# RSG_1_0.net
KiCad netlist of a schematic drawn in EAGLE
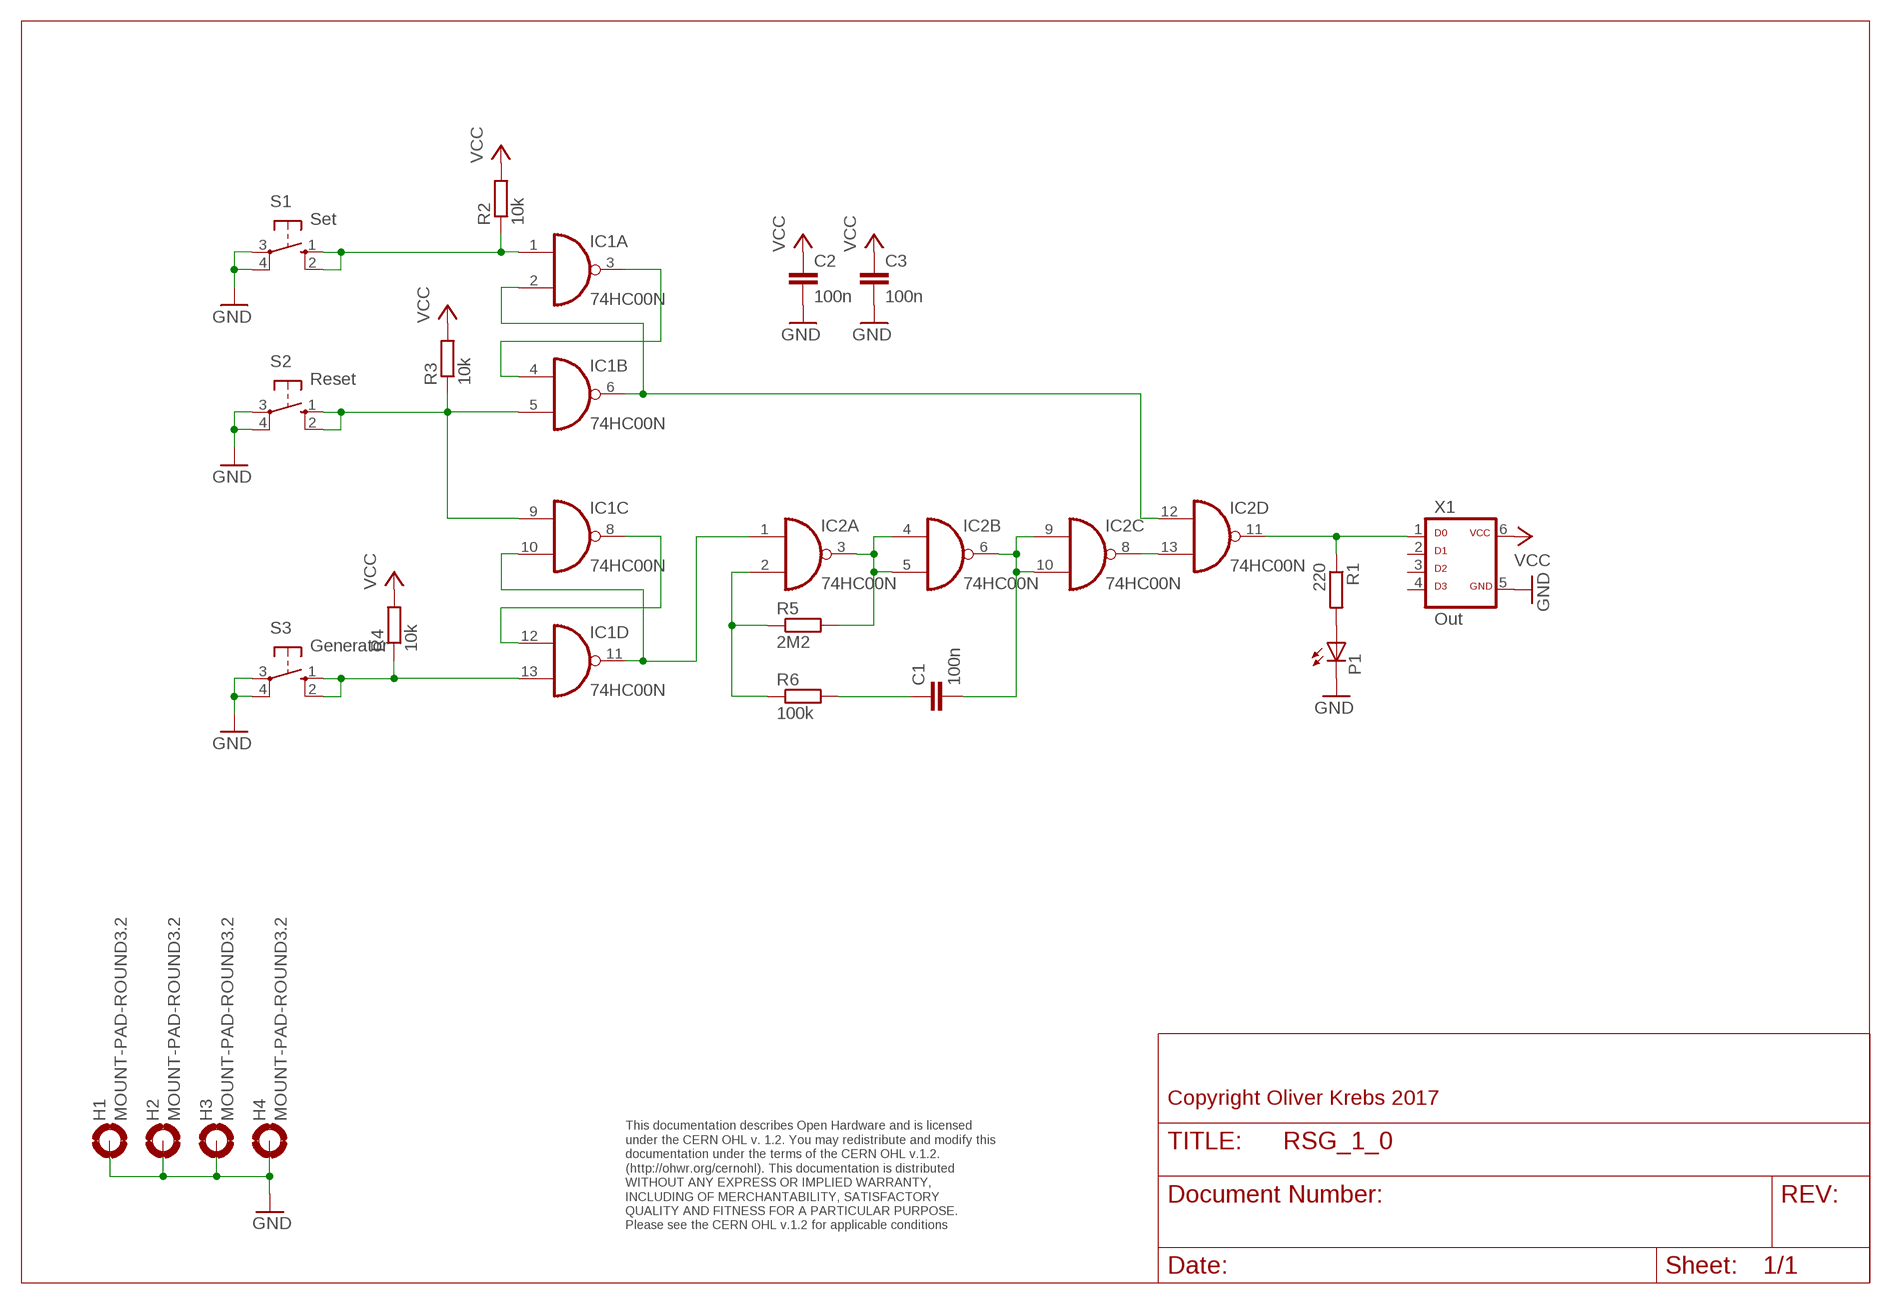
[diagram p0: schematic, sheet 1]

(export (version "E")
  (design (tool "Eeschema 10.0.6"))
  (components
    (comp (ref "C1")
      (value "100n")
      (footprint "eagle-import:C050-025X075")
      (libsource (lib "eagle-import") (part "C-EU050-025X075"))
    )
    (comp (ref "C2")
      (value "100n")
      (footprint "eagle-import:C050-025X075")
      (libsource (lib "eagle-import") (part "C-EU050-025X075"))
    )
    (comp (ref "C3")
      (value "100n")
      (footprint "eagle-import:C050-025X075")
      (libsource (lib "eagle-import") (part "C-EU050-025X075"))
    )
    (comp (ref "H1")
      (value "MOUNT-PAD-ROUND3.2")
      (footprint "eagle-import:3,2-PAD")
      (libsource (lib "eagle-import") (part "MOUNT-PAD-ROUND3.2"))
    )
    (comp (ref "H2")
      (value "MOUNT-PAD-ROUND3.2")
      (footprint "eagle-import:3,2-PAD")
      (libsource (lib "eagle-import") (part "MOUNT-PAD-ROUND3.2"))
    )
    (comp (ref "H3")
      (value "MOUNT-PAD-ROUND3.2")
      (footprint "eagle-import:3,2-PAD")
      (libsource (lib "eagle-import") (part "MOUNT-PAD-ROUND3.2"))
    )
    (comp (ref "H4")
      (value "MOUNT-PAD-ROUND3.2")
      (footprint "eagle-import:3,2-PAD")
      (libsource (lib "eagle-import") (part "MOUNT-PAD-ROUND3.2"))
    )
    (comp (ref "IC1")
      (value "74HC00N")
      (footprint "eagle-import:DIL14")
      (libsource (lib "eagle-import") (part "7400NHC"))
    )
    (comp (ref "IC2")
      (value "74HC00N")
      (footprint "eagle-import:DIL14")
      (libsource (lib "eagle-import") (part "7400NHC"))
    )
    (comp (ref "P1")
      (value "LED3MM")
      (footprint "eagle-import:LED3MM")
      (libsource (lib "eagle-import") (part "LED3MM"))
    )
    (comp (ref "R1")
      (value "220")
      (footprint "eagle-import:0207_10")
      (libsource (lib "eagle-import") (part "R-EU_0207/10"))
    )
    (comp (ref "R2")
      (value "10k")
      (footprint "eagle-import:0207_10")
      (libsource (lib "eagle-import") (part "R-EU_0207/10"))
    )
    (comp (ref "R3")
      (value "10k")
      (footprint "eagle-import:0207_10")
      (libsource (lib "eagle-import") (part "R-EU_0207/10"))
    )
    (comp (ref "R4")
      (value "10k")
      (footprint "eagle-import:0207_10")
      (libsource (lib "eagle-import") (part "R-EU_0207/10"))
    )
    (comp (ref "R5")
      (value "2M2")
      (footprint "eagle-import:0207_10")
      (libsource (lib "eagle-import") (part "R-EU_0207/10"))
    )
    (comp (ref "R6")
      (value "100k")
      (footprint "eagle-import:0207_10")
      (libsource (lib "eagle-import") (part "R-EU_0207/10"))
    )
    (comp (ref "S1")
      (value "Set")
      (footprint "eagle-import:B3F-10XX")
      (fields (field (name "MPN") "B3F-1000"))
      (libsource (lib "eagle-import") (part "10-XX"))
    )
    (comp (ref "S2")
      (value "Reset")
      (footprint "eagle-import:B3F-10XX")
      (fields (field (name "MPN") "B3F-1000"))
      (libsource (lib "eagle-import") (part "10-XX"))
    )
    (comp (ref "S3")
      (value "Generator")
      (footprint "eagle-import:B3F-10XX")
      (fields (field (name "MPN") "B3F-1000"))
      (libsource (lib "eagle-import") (part "10-XX"))
    )
    (comp (ref "X1")
      (value "Out")
      (footprint "eagle-import:ML-6")
      (libsource (lib "eagle-import") (part "ML6D"))
    )
  )
  (nets
    (net (code "1") (name "GND") (class "Default")
      (node (ref "C2") (pin "2") (pinfunction "2_2") (pintype "passive"))
      (node (ref "C3") (pin "2") (pinfunction "2_2") (pintype "passive"))
      (node (ref "H1") (pin "B3,2") (pinfunction "MOUNT_B3,2") (pintype "passive"))
      (node (ref "H2") (pin "B3,2") (pinfunction "MOUNT_B3,2") (pintype "passive"))
      (node (ref "H3") (pin "B3,2") (pinfunction "MOUNT_B3,2") (pintype "passive"))
      (node (ref "H4") (pin "B3,2") (pinfunction "MOUNT_B3,2") (pintype "passive"))
      (node (ref "P1") (pin "K") (pinfunction "C_K") (pintype "passive"))
      (node (ref "S1") (pin "3") (pinfunction "P_3") (pintype "passive"))
      (node (ref "S1") (pin "4") (pinfunction "P1_4") (pintype "passive"))
      (node (ref "S2") (pin "3") (pinfunction "P_3") (pintype "passive"))
      (node (ref "S2") (pin "4") (pinfunction "P1_4") (pintype "passive"))
      (node (ref "S3") (pin "3") (pinfunction "P_3") (pintype "passive"))
      (node (ref "S3") (pin "4") (pinfunction "P1_4") (pintype "passive"))
      (node (ref "X1") (pin "5") (pinfunction "5_5") (pintype "passive"))
    )
    (net (code "2") (name "Net-(C1-Pad1)") (class "Default")
      (node (ref "C1") (pin "1") (pinfunction "1_1") (pintype "passive"))
      (node (ref "R6") (pin "2") (pinfunction "2_2") (pintype "passive"))
    )
    (net (code "3") (name "Net-(IC1A-I0)") (class "Default")
      (node (ref "IC1") (pin "1") (pinfunction "I0_1") (pintype "input"))
      (node (ref "R2") (pin "1") (pinfunction "1_1") (pintype "passive"))
      (node (ref "S1") (pin "1") (pinfunction "S_1") (pintype "passive"))
      (node (ref "S1") (pin "2") (pinfunction "S1_2") (pintype "passive"))
    )
    (net (code "4") (name "Net-(IC1A-I1)") (class "Default")
      (node (ref "IC1") (pin "2") (pinfunction "I1_2") (pintype "input"))
      (node (ref "IC1") (pin "6") (pinfunction "O_6") (pintype "output"))
      (node (ref "IC2") (pin "12") (pinfunction "I0_12") (pintype "input"))
    )
    (net (code "5") (name "Net-(IC1A-O)") (class "Default")
      (node (ref "IC1") (pin "3") (pinfunction "O_3") (pintype "output"))
      (node (ref "IC1") (pin "4") (pinfunction "I0_4") (pintype "input"))
    )
    (net (code "6") (name "Net-(IC1B-I1)") (class "Default")
      (node (ref "IC1") (pin "5") (pinfunction "I1_5") (pintype "input"))
      (node (ref "IC1") (pin "9") (pinfunction "I0_9") (pintype "input"))
      (node (ref "R3") (pin "1") (pinfunction "1_1") (pintype "passive"))
      (node (ref "S2") (pin "1") (pinfunction "S_1") (pintype "passive"))
      (node (ref "S2") (pin "2") (pinfunction "S1_2") (pintype "passive"))
    )
    (net (code "7") (name "Net-(IC1C-I1)") (class "Default")
      (node (ref "IC1") (pin "10") (pinfunction "I1_10") (pintype "input"))
      (node (ref "IC1") (pin "11") (pinfunction "O_11") (pintype "output"))
      (node (ref "IC2") (pin "1") (pinfunction "I0_1") (pintype "input"))
    )
    (net (code "8") (name "Net-(IC1C-O)") (class "Default")
      (node (ref "IC1") (pin "12") (pinfunction "I0_12") (pintype "input"))
      (node (ref "IC1") (pin "8") (pinfunction "O_8") (pintype "output"))
    )
    (net (code "9") (name "Net-(IC1D-I1)") (class "Default")
      (node (ref "IC1") (pin "13") (pinfunction "I1_13") (pintype "input"))
      (node (ref "R4") (pin "1") (pinfunction "1_1") (pintype "passive"))
      (node (ref "S3") (pin "1") (pinfunction "S_1") (pintype "passive"))
      (node (ref "S3") (pin "2") (pinfunction "S1_2") (pintype "passive"))
    )
    (net (code "10") (name "Net-(IC2A-I1)") (class "Default")
      (node (ref "IC2") (pin "2") (pinfunction "I1_2") (pintype "input"))
      (node (ref "R5") (pin "1") (pinfunction "1_1") (pintype "passive"))
      (node (ref "R6") (pin "1") (pinfunction "1_1") (pintype "passive"))
    )
    (net (code "11") (name "Net-(IC2A-O)") (class "Default")
      (node (ref "IC2") (pin "3") (pinfunction "O_3") (pintype "output"))
      (node (ref "IC2") (pin "4") (pinfunction "I0_4") (pintype "input"))
      (node (ref "IC2") (pin "5") (pinfunction "I1_5") (pintype "input"))
      (node (ref "R5") (pin "2") (pinfunction "2_2") (pintype "passive"))
    )
    (net (code "12") (name "Net-(IC2B-O)") (class "Default")
      (node (ref "C1") (pin "2") (pinfunction "2_2") (pintype "passive"))
      (node (ref "IC2") (pin "10") (pinfunction "I1_10") (pintype "input"))
      (node (ref "IC2") (pin "6") (pinfunction "O_6") (pintype "output"))
      (node (ref "IC2") (pin "9") (pinfunction "I0_9") (pintype "input"))
    )
    (net (code "13") (name "Net-(IC2C-O)") (class "Default")
      (node (ref "IC2") (pin "13") (pinfunction "I1_13") (pintype "input"))
      (node (ref "IC2") (pin "8") (pinfunction "O_8") (pintype "output"))
    )
    (net (code "14") (name "Net-(IC2D-O)") (class "Default")
      (node (ref "IC2") (pin "11") (pinfunction "O_11") (pintype "output"))
      (node (ref "R1") (pin "1") (pinfunction "1_1") (pintype "passive"))
      (node (ref "X1") (pin "1") (pinfunction "1_1") (pintype "passive"))
    )
    (net (code "15") (name "Net-(P1-PadA)") (class "Default")
      (node (ref "P1") (pin "A") (pinfunction "A_A") (pintype "passive"))
      (node (ref "R1") (pin "2") (pinfunction "2_2") (pintype "passive"))
    )
    (net (code "16") (name "VCC") (class "Default")
      (node (ref "C2") (pin "1") (pinfunction "1_1") (pintype "passive"))
      (node (ref "C3") (pin "1") (pinfunction "1_1") (pintype "passive"))
      (node (ref "R2") (pin "2") (pinfunction "2_2") (pintype "passive"))
      (node (ref "R3") (pin "2") (pinfunction "2_2") (pintype "passive"))
      (node (ref "R4") (pin "2") (pinfunction "2_2") (pintype "passive"))
      (node (ref "X1") (pin "6") (pinfunction "6_6") (pintype "passive"))
    )
    (net (code "17") (name "unconnected-(X1-Pad2)") (class "Default")
      (node (ref "X1") (pin "2") (pinfunction "2_2") (pintype "passive"))
    )
    (net (code "18") (name "unconnected-(X1-Pad3)") (class "Default")
      (node (ref "X1") (pin "3") (pinfunction "3_3") (pintype "passive"))
    )
    (net (code "19") (name "unconnected-(X1-Pad4)") (class "Default")
      (node (ref "X1") (pin "4") (pinfunction "4_4") (pintype "passive"))
    )
  )
)
